# Motor_Control.net
KiCad netlist of a schematic drawn in Altium Designer
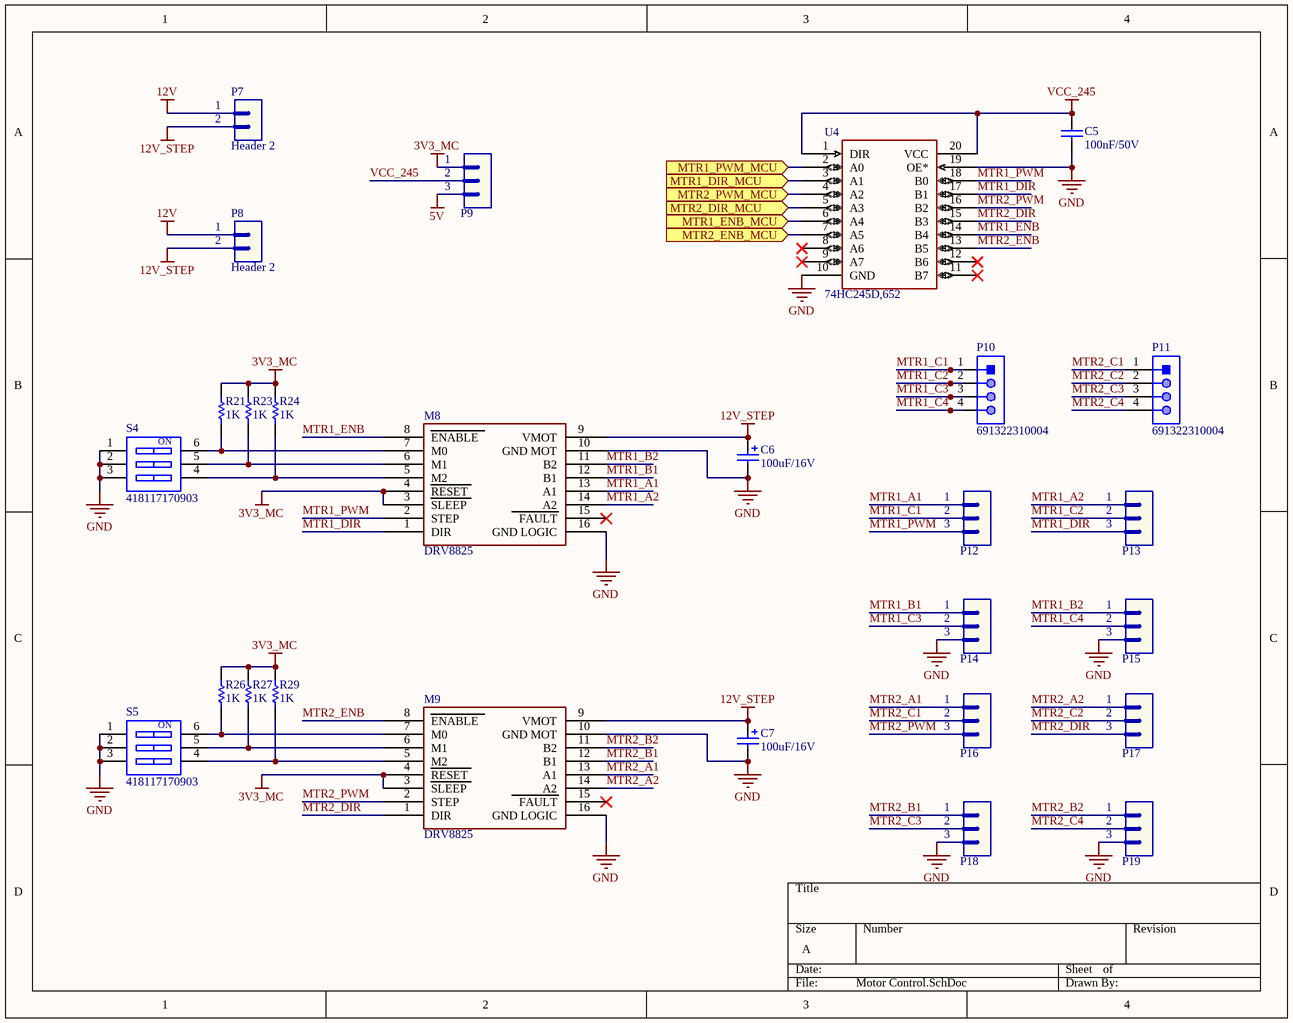
[diagram p0: Motor Control.SchDoc]

(export (version "E")
  (design (tool "Eeschema 10.0.6"))
  (components
    (comp (ref "C5")
      (value "100nF/50V")
      (footprint "CAP-SM-0805")
      (description "CAP CER 0.1UF 50V Y5V 0805")
      (fields
        (field (name "MANUFACTURER") "Samsung Electro-Mechanics")
        (field (name "MANUFACTURER PART NUMBER") "CL21F104ZBCNNNC")
      )
      (libsource (lib "Capacitor") (part "Cap-100nF-50V-0805"))
    )
    (comp (ref "C6")
      (value "100uF/16V")
      (footprint "Capacitor:CAP-SM-AL-SIZE-D-D6L6")
      (description "CAP ALUM 100UF 20% 16V SMD")
      (fields
        (field (name "MANUFACTURER") "Nichicon")
        (field (name "MANUFACTURER PART NUMBER") "UWX1C101MCL1GB")
      )
      (libsource (lib "Capacitor") (part "Cap-Al-100uF-16V-D6L5"))
    )
    (comp (ref "C7")
      (value "100uF/16V")
      (footprint "Capacitor:CAP-SM-AL-SIZE-D-D6L6")
      (description "CAP ALUM 100UF 20% 16V SMD")
      (fields
        (field (name "MANUFACTURER") "Nichicon")
        (field (name "MANUFACTURER PART NUMBER") "UWX1C101MCL1GB")
      )
      (libsource (lib "Capacitor") (part "Cap-Al-100uF-16V-D6L5"))
    )
    (comp (ref "M8")
      (value "DRV8825")
      (footprint "DRV8825")
      (fields (field (name "LOCAL SUPPLIER PART NUMBER") "HS000686"))
      (libsource (lib "PIF_robot") (part "DRV8825"))
    )
    (comp (ref "M9")
      (value "DRV8825")
      (footprint "DRV8825")
      (fields (field (name "LOCAL SUPPLIER PART NUMBER") "HS000686"))
      (libsource (lib "PIF_robot") (part "DRV8825"))
    )
    (comp (ref "P7")
      (value "Header 2")
      (footprint "JP2")
      (description "Header, 2-Pin")
      (fields (field (name "PUBLISHER") "Altium Limited"))
      (libsource (lib "PIF_C16_lib") (part "Header 2"))
    )
    (comp (ref "P8")
      (value "Header 2")
      (footprint "JP2")
      (description "Header, 2-Pin")
      (fields (field (name "PUBLISHER") "Altium Limited"))
      (libsource (lib "PIF_C16_lib") (part "Header 2"))
    )
    (comp (ref "P9")
      (value "Header 3")
      (footprint "JP3")
      (description "Header, 3-Pin")
      (fields (field (name "PUBLISHER") "Altium Limited"))
      (libsource (lib "Header-Connector") (part "Header 3"))
    )
    (comp (ref "P10")
      (value "691322310004")
      (footprint "691322310004")
      (description "WR-TBL Serie 322 Horizontal PCB Header, Pluggable, pitch 3.81mm, 4p")
      (fields (field (name "PUBLISHER") "Wurth Elektronik"))
      (libsource (lib "691322310002_Altium_WR-TBL_rev19a") (part "691322310004"))
    )
    (comp (ref "P11")
      (value "691322310004")
      (footprint "691322310004")
      (description "WR-TBL Serie 322 Horizontal PCB Header, Pluggable, pitch 3.81mm, 4p")
      (fields (field (name "PUBLISHER") "Wurth Elektronik"))
      (libsource (lib "691322310002_Altium_WR-TBL_rev19a") (part "691322310004"))
    )
    (comp (ref "P12")
      (value "Header 3")
      (footprint "JP3")
      (description "Header, 3-Pin")
      (fields (field (name "PUBLISHER") "Altium Limited"))
      (libsource (lib "Header-Connector") (part "Header 3"))
    )
    (comp (ref "P13")
      (value "Header 3")
      (footprint "JP3")
      (description "Header, 3-Pin")
      (fields (field (name "PUBLISHER") "Altium Limited"))
      (libsource (lib "Header-Connector") (part "Header 3"))
    )
    (comp (ref "P14")
      (value "Header 3")
      (footprint "JP3")
      (description "Header, 3-Pin")
      (fields (field (name "PUBLISHER") "Altium Limited"))
      (libsource (lib "Header-Connector") (part "Header 3"))
    )
    (comp (ref "P15")
      (value "Header 3")
      (footprint "JP3")
      (description "Header, 3-Pin")
      (fields (field (name "PUBLISHER") "Altium Limited"))
      (libsource (lib "Header-Connector") (part "Header 3"))
    )
    (comp (ref "P16")
      (value "Header 3")
      (footprint "JP3")
      (description "Header, 3-Pin")
      (fields (field (name "PUBLISHER") "Altium Limited"))
      (libsource (lib "Header-Connector") (part "Header 3"))
    )
    (comp (ref "P17")
      (value "Header 3")
      (footprint "JP3")
      (description "Header, 3-Pin")
      (fields (field (name "PUBLISHER") "Altium Limited"))
      (libsource (lib "Header-Connector") (part "Header 3"))
    )
    (comp (ref "P18")
      (value "Header 3")
      (footprint "JP3")
      (description "Header, 3-Pin")
      (fields (field (name "PUBLISHER") "Altium Limited"))
      (libsource (lib "Header-Connector") (part "Header 3"))
    )
    (comp (ref "P19")
      (value "Header 3")
      (footprint "JP3")
      (description "Header, 3-Pin")
      (fields (field (name "PUBLISHER") "Altium Limited"))
      (libsource (lib "Header-Connector") (part "Header 3"))
    )
    (comp (ref "R21")
      (value "1K")
      (footprint "RES-SM-0805")
      (description "RES 1K OHM 1% 1/4W 0805")
      (fields
        (field (name "MANUFACTURER") "Stackpole Electronics Inc")
        (field (name "MANUFACTURER PART NUMBER") "RNCP0805FTD1K00")
      )
      (libsource (lib "Resistor") (part "Res-1K-0805"))
    )
    (comp (ref "R23")
      (value "1K")
      (footprint "RES-SM-0805")
      (description "RES 1K OHM 1% 1/4W 0805")
      (fields
        (field (name "MANUFACTURER") "Stackpole Electronics Inc")
        (field (name "MANUFACTURER PART NUMBER") "RNCP0805FTD1K00")
      )
      (libsource (lib "Resistor") (part "Res-1K-0805"))
    )
    (comp (ref "R24")
      (value "1K")
      (footprint "RES-SM-0805")
      (description "RES 1K OHM 1% 1/4W 0805")
      (fields
        (field (name "MANUFACTURER") "Stackpole Electronics Inc")
        (field (name "MANUFACTURER PART NUMBER") "RNCP0805FTD1K00")
      )
      (libsource (lib "Resistor") (part "Res-1K-0805"))
    )
    (comp (ref "R26")
      (value "1K")
      (footprint "Resistor:RES-SM-0805")
      (description "RES 1K OHM 1% 1/4W 0805")
      (fields
        (field (name "MANUFACTURER") "Stackpole Electronics Inc")
        (field (name "MANUFACTURER PART NUMBER") "RNCP0805FTD1K00")
      )
      (libsource (lib "Resistor") (part "Res-1K-0805"))
    )
    (comp (ref "R27")
      (value "1K")
      (footprint "Resistor:RES-SM-0805")
      (description "RES 1K OHM 1% 1/4W 0805")
      (fields
        (field (name "MANUFACTURER") "Stackpole Electronics Inc")
        (field (name "MANUFACTURER PART NUMBER") "RNCP0805FTD1K00")
      )
      (libsource (lib "Resistor") (part "Res-1K-0805"))
    )
    (comp (ref "R29")
      (value "1K")
      (footprint "Resistor:RES-SM-0805")
      (description "RES 1K OHM 1% 1/4W 0805")
      (fields
        (field (name "MANUFACTURER") "Stackpole Electronics Inc")
        (field (name "MANUFACTURER PART NUMBER") "RNCP0805FTD1K00")
      )
      (libsource (lib "Resistor") (part "Res-1K-0805"))
    )
    (comp (ref "S4")
      (value "418117170903")
      (footprint "418117170903")
      (description "WS-DITV Compact THT Dip Switch, Flat Actuator, pitch 2.54mm, 3p")
      (fields (field (name "PUBLISHER") "Wurth Elektronik"))
      (libsource (lib "418117170903_Altium_WS-DITV_rev19a") (part "418117170903"))
    )
    (comp (ref "S5")
      (value "418117170903")
      (footprint "418117170903")
      (description "WS-DITV Compact THT Dip Switch, Flat Actuator, pitch 2.54mm, 3p")
      (fields (field (name "PUBLISHER") "Wurth Elektronik"))
      (libsource (lib "418117170903_Altium_WS-DITV_rev19a") (part "418117170903"))
    )
    (comp (ref "U4")
      (value "74HC245D,652")
      (footprint "SOT163-1_NEX")
      (libsource (lib "PIF_robot") (part "74HC245D,652"))
    )
  )
  (nets
    (net (code "1") (name "/MTR1_A1") (class "Default")
      (node (ref "M8") (pin "13") (pinfunction "A1_13") (pintype "passive"))
      (node (ref "P12") (pin "1") (pinfunction "1_1") (pintype "passive"))
    )
    (net (code "2") (name "/MTR1_A2") (class "Default")
      (node (ref "M8") (pin "14") (pinfunction "A2_14") (pintype "passive"))
      (node (ref "P13") (pin "1") (pinfunction "1_1") (pintype "passive"))
    )
    (net (code "3") (name "/MTR1_B1") (class "Default")
      (node (ref "M8") (pin "12") (pinfunction "B1_12") (pintype "passive"))
      (node (ref "P14") (pin "1") (pinfunction "1_1") (pintype "passive"))
    )
    (net (code "4") (name "/MTR1_B2") (class "Default")
      (node (ref "M8") (pin "11") (pinfunction "B2_11") (pintype "passive"))
      (node (ref "P15") (pin "1") (pinfunction "1_1") (pintype "passive"))
    )
    (net (code "5") (name "/MTR1_C1") (class "Default")
      (node (ref "P10") (pin "1") (pinfunction "1_1") (pintype "passive"))
      (node (ref "P12") (pin "2") (pinfunction "2_2") (pintype "passive"))
    )
    (net (code "6") (name "/MTR1_C2") (class "Default")
      (node (ref "P10") (pin "2") (pinfunction "2_2") (pintype "passive"))
      (node (ref "P13") (pin "2") (pinfunction "2_2") (pintype "passive"))
    )
    (net (code "7") (name "/MTR1_C3") (class "Default")
      (node (ref "P10") (pin "3") (pinfunction "3_3") (pintype "passive"))
      (node (ref "P14") (pin "2") (pinfunction "2_2") (pintype "passive"))
    )
    (net (code "8") (name "/MTR1_C4") (class "Default")
      (node (ref "P10") (pin "4") (pinfunction "4_4") (pintype "passive"))
      (node (ref "P15") (pin "2") (pinfunction "2_2") (pintype "passive"))
    )
    (net (code "9") (name "/MTR1_DIR") (class "Default")
      (node (ref "M8") (pin "1") (pinfunction "DIR_1") (pintype "passive"))
      (node (ref "P13") (pin "3") (pinfunction "3_3") (pintype "passive"))
      (node (ref "U4") (pin "17") (pinfunction "B1_17") (pintype "bidirectional"))
    )
    (net (code "10") (name "/MTR1_DIR_MCU") (class "Default")
      (node (ref "U4") (pin "3") (pinfunction "A1_3") (pintype "bidirectional"))
    )
    (net (code "11") (name "/MTR1_ENB") (class "Default")
      (node (ref "M8") (pin "8") (pinfunction "ENABLE_8") (pintype "passive"))
      (node (ref "U4") (pin "14") (pinfunction "B4_14") (pintype "bidirectional"))
    )
    (net (code "12") (name "/MTR1_ENB_MCU") (class "Default")
      (node (ref "U4") (pin "6") (pinfunction "A4_6") (pintype "bidirectional"))
    )
    (net (code "13") (name "/MTR1_PWM") (class "Default")
      (node (ref "M8") (pin "2") (pinfunction "STEP_2") (pintype "passive"))
      (node (ref "P12") (pin "3") (pinfunction "3_3") (pintype "passive"))
      (node (ref "U4") (pin "18") (pinfunction "B0_18") (pintype "bidirectional"))
    )
    (net (code "14") (name "/MTR1_PWM_MCU") (class "Default")
      (node (ref "U4") (pin "2") (pinfunction "A0_2") (pintype "bidirectional"))
    )
    (net (code "15") (name "/MTR2_A1") (class "Default")
      (node (ref "M9") (pin "13") (pinfunction "A1_13") (pintype "passive"))
      (node (ref "P16") (pin "1") (pinfunction "1_1") (pintype "passive"))
    )
    (net (code "16") (name "/MTR2_A2") (class "Default")
      (node (ref "M9") (pin "14") (pinfunction "A2_14") (pintype "passive"))
      (node (ref "P17") (pin "1") (pinfunction "1_1") (pintype "passive"))
    )
    (net (code "17") (name "/MTR2_B1") (class "Default")
      (node (ref "M9") (pin "12") (pinfunction "B1_12") (pintype "passive"))
      (node (ref "P18") (pin "1") (pinfunction "1_1") (pintype "passive"))
    )
    (net (code "18") (name "/MTR2_B2") (class "Default")
      (node (ref "M9") (pin "11") (pinfunction "B2_11") (pintype "passive"))
      (node (ref "P19") (pin "1") (pinfunction "1_1") (pintype "passive"))
    )
    (net (code "19") (name "/MTR2_C1") (class "Default")
      (node (ref "P11") (pin "1") (pinfunction "1_1") (pintype "passive"))
      (node (ref "P16") (pin "2") (pinfunction "2_2") (pintype "passive"))
    )
    (net (code "20") (name "/MTR2_C2") (class "Default")
      (node (ref "P11") (pin "2") (pinfunction "2_2") (pintype "passive"))
      (node (ref "P17") (pin "2") (pinfunction "2_2") (pintype "passive"))
    )
    (net (code "21") (name "/MTR2_C3") (class "Default")
      (node (ref "P11") (pin "3") (pinfunction "3_3") (pintype "passive"))
      (node (ref "P18") (pin "2") (pinfunction "2_2") (pintype "passive"))
    )
    (net (code "22") (name "/MTR2_C4") (class "Default")
      (node (ref "P11") (pin "4") (pinfunction "4_4") (pintype "passive"))
      (node (ref "P19") (pin "2") (pinfunction "2_2") (pintype "passive"))
    )
    (net (code "23") (name "/MTR2_DIR") (class "Default")
      (node (ref "M9") (pin "1") (pinfunction "DIR_1") (pintype "passive"))
      (node (ref "P17") (pin "3") (pinfunction "3_3") (pintype "passive"))
      (node (ref "U4") (pin "15") (pinfunction "B3_15") (pintype "bidirectional"))
    )
    (net (code "24") (name "/MTR2_DIR_MCU") (class "Default")
      (node (ref "U4") (pin "5") (pinfunction "A3_5") (pintype "bidirectional"))
    )
    (net (code "25") (name "/MTR2_ENB") (class "Default")
      (node (ref "M9") (pin "8") (pinfunction "ENABLE_8") (pintype "passive"))
      (node (ref "U4") (pin "13") (pinfunction "B5_13") (pintype "bidirectional"))
    )
    (net (code "26") (name "/MTR2_ENB_MCU") (class "Default")
      (node (ref "U4") (pin "7") (pinfunction "A5_7") (pintype "bidirectional"))
    )
    (net (code "27") (name "/MTR2_PWM") (class "Default")
      (node (ref "M9") (pin "2") (pinfunction "STEP_2") (pintype "passive"))
      (node (ref "P16") (pin "3") (pinfunction "3_3") (pintype "passive"))
      (node (ref "U4") (pin "16") (pinfunction "B2_16") (pintype "bidirectional"))
    )
    (net (code "28") (name "/MTR2_PWM_MCU") (class "Default")
      (node (ref "U4") (pin "4") (pinfunction "A2_4") (pintype "bidirectional"))
    )
    (net (code "29") (name "3V3_MC") (class "Default")
      (node (ref "M8") (pin "3") (pinfunction "SLEEP_3") (pintype "passive"))
      (node (ref "M8") (pin "4") (pinfunction "RESET_4") (pintype "passive"))
      (node (ref "M9") (pin "3") (pinfunction "SLEEP_3") (pintype "passive"))
      (node (ref "M9") (pin "4") (pinfunction "RESET_4") (pintype "passive"))
      (node (ref "P9") (pin "1") (pinfunction "1_1") (pintype "passive"))
      (node (ref "R21") (pin "2") (pinfunction "2_2") (pintype "passive"))
      (node (ref "R23") (pin "2") (pinfunction "2_2") (pintype "passive"))
      (node (ref "R24") (pin "2") (pinfunction "2_2") (pintype "passive"))
      (node (ref "R26") (pin "2") (pinfunction "2_2") (pintype "passive"))
      (node (ref "R27") (pin "2") (pinfunction "2_2") (pintype "passive"))
      (node (ref "R29") (pin "2") (pinfunction "2_2") (pintype "passive"))
    )
    (net (code "30") (name "5V") (class "Default")
      (node (ref "P9") (pin "3") (pinfunction "3_3") (pintype "passive"))
    )
    (net (code "31") (name "12V") (class "Default")
      (node (ref "P7") (pin "1") (pinfunction "1_1") (pintype "passive"))
      (node (ref "P8") (pin "1") (pinfunction "1_1") (pintype "passive"))
    )
    (net (code "32") (name "12V_STEP") (class "Default")
      (node (ref "C6") (pin "1") (pinfunction "1_1") (pintype "passive"))
      (node (ref "C7") (pin "1") (pinfunction "1_1") (pintype "passive"))
      (node (ref "M8") (pin "9") (pinfunction "VMOT_9") (pintype "passive"))
      (node (ref "M9") (pin "9") (pinfunction "VMOT_9") (pintype "passive"))
      (node (ref "P7") (pin "2") (pinfunction "2_2") (pintype "passive"))
      (node (ref "P8") (pin "2") (pinfunction "2_2") (pintype "passive"))
    )
    (net (code "33") (name "GND") (class "Default")
      (node (ref "C5") (pin "1") (pinfunction "1_1") (pintype "passive"))
      (node (ref "C6") (pin "2") (pinfunction "2_2") (pintype "passive"))
      (node (ref "C7") (pin "2") (pinfunction "2_2") (pintype "passive"))
      (node (ref "M8") (pin "10") (pinfunction "GND_MOT_10") (pintype "passive"))
      (node (ref "M8") (pin "16") (pinfunction "GND_LOGIC_16") (pintype "passive"))
      (node (ref "M9") (pin "10") (pinfunction "GND_MOT_10") (pintype "passive"))
      (node (ref "M9") (pin "16") (pinfunction "GND_LOGIC_16") (pintype "passive"))
      (node (ref "P14") (pin "3") (pinfunction "3_3") (pintype "passive"))
      (node (ref "P15") (pin "3") (pinfunction "3_3") (pintype "passive"))
      (node (ref "P18") (pin "3") (pinfunction "3_3") (pintype "passive"))
      (node (ref "P19") (pin "3") (pinfunction "3_3") (pintype "passive"))
      (node (ref "S4") (pin "1") (pinfunction "1_1") (pintype "passive"))
      (node (ref "S4") (pin "2") (pinfunction "2_2") (pintype "passive"))
      (node (ref "S4") (pin "3") (pinfunction "3_3") (pintype "passive"))
      (node (ref "S5") (pin "1") (pinfunction "1_1") (pintype "passive"))
      (node (ref "S5") (pin "2") (pinfunction "2_2") (pintype "passive"))
      (node (ref "S5") (pin "3") (pinfunction "3_3") (pintype "passive"))
      (node (ref "U4") (pin "10") (pinfunction "GND_10") (pintype "power_in"))
      (node (ref "U4") (pin "19") (pinfunction "OE*_19") (pintype "input"))
    )
    (net (code "34") (name "Net-(M8-M0)") (class "Default")
      (node (ref "M8") (pin "7") (pinfunction "M0_7") (pintype "passive"))
      (node (ref "R21") (pin "1") (pinfunction "1_1") (pintype "passive"))
      (node (ref "S4") (pin "6") (pinfunction "6_6") (pintype "passive"))
    )
    (net (code "35") (name "Net-(M8-M1)") (class "Default")
      (node (ref "M8") (pin "6") (pinfunction "M1_6") (pintype "passive"))
      (node (ref "R23") (pin "1") (pinfunction "1_1") (pintype "passive"))
      (node (ref "S4") (pin "5") (pinfunction "5_5") (pintype "passive"))
    )
    (net (code "36") (name "Net-(M8-M2)") (class "Default")
      (node (ref "M8") (pin "5") (pinfunction "M2_5") (pintype "passive"))
      (node (ref "R24") (pin "1") (pinfunction "1_1") (pintype "passive"))
      (node (ref "S4") (pin "4") (pinfunction "4_4") (pintype "passive"))
    )
    (net (code "37") (name "Net-(M9-M0)") (class "Default")
      (node (ref "M9") (pin "7") (pinfunction "M0_7") (pintype "passive"))
      (node (ref "R26") (pin "1") (pinfunction "1_1") (pintype "passive"))
      (node (ref "S5") (pin "6") (pinfunction "6_6") (pintype "passive"))
    )
    (net (code "38") (name "Net-(M9-M1)") (class "Default")
      (node (ref "M9") (pin "6") (pinfunction "M1_6") (pintype "passive"))
      (node (ref "R27") (pin "1") (pinfunction "1_1") (pintype "passive"))
      (node (ref "S5") (pin "5") (pinfunction "5_5") (pintype "passive"))
    )
    (net (code "39") (name "Net-(M9-M2)") (class "Default")
      (node (ref "M9") (pin "5") (pinfunction "M2_5") (pintype "passive"))
      (node (ref "R29") (pin "1") (pinfunction "1_1") (pintype "passive"))
      (node (ref "S5") (pin "4") (pinfunction "4_4") (pintype "passive"))
    )
    (net (code "40") (name "VCC_245") (class "Default")
      (node (ref "C5") (pin "2") (pinfunction "2_2") (pintype "passive"))
      (node (ref "P9") (pin "2") (pinfunction "2_2") (pintype "passive"))
      (node (ref "U4") (pin "1") (pinfunction "DIR_1") (pintype "input"))
      (node (ref "U4") (pin "20") (pinfunction "VCC_20") (pintype "power_in"))
    )
    (net (code "41") (name "unconnected-(M8-FAULT-Pad15)") (class "Default")
      (node (ref "M8") (pin "15") (pinfunction "FAULT_15") (pintype "passive+no_connect"))
    )
    (net (code "42") (name "unconnected-(M9-FAULT-Pad15)") (class "Default")
      (node (ref "M9") (pin "15") (pinfunction "FAULT_15") (pintype "passive+no_connect"))
    )
    (net (code "43") (name "unconnected-(U4-A6-Pad8)") (class "Default")
      (node (ref "U4") (pin "8") (pinfunction "A6_8") (pintype "bidirectional+no_connect"))
    )
    (net (code "44") (name "unconnected-(U4-A7-Pad9)") (class "Default")
      (node (ref "U4") (pin "9") (pinfunction "A7_9") (pintype "bidirectional+no_connect"))
    )
    (net (code "45") (name "unconnected-(U4-B6-Pad12)") (class "Default")
      (node (ref "U4") (pin "12") (pinfunction "B6_12") (pintype "bidirectional+no_connect"))
    )
    (net (code "46") (name "unconnected-(U4-B7-Pad11)") (class "Default")
      (node (ref "U4") (pin "11") (pinfunction "B7_11") (pintype "bidirectional+no_connect"))
    )
  )
)
